# PR9014.net
KiCad netlist of a schematic drawn in EAGLE
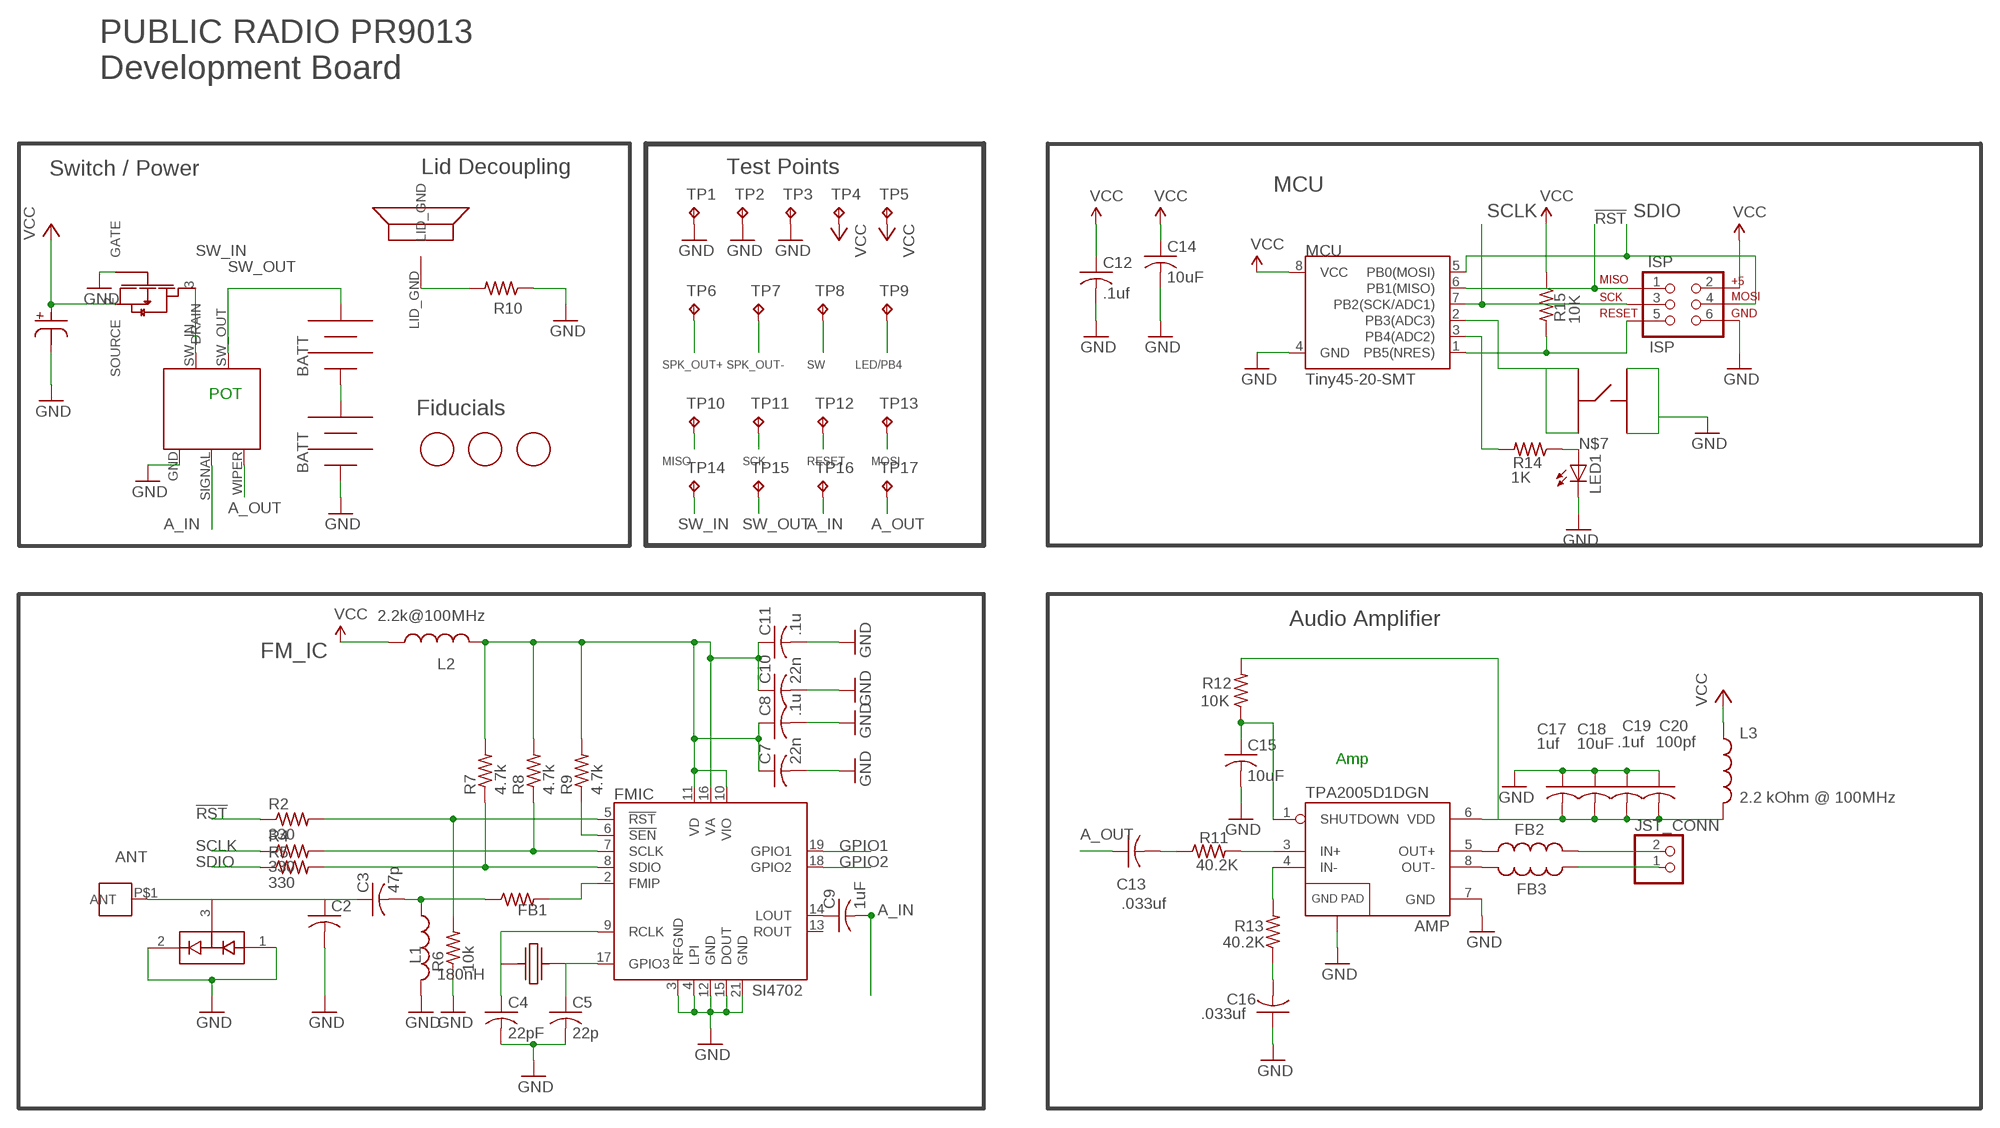
[diagram p0: schematic, sheet 1]

(export (version "E")
  (design (tool "Eeschema 10.0.6"))
  (components
    (comp (ref "AMP")
      (value "TPA2005D1DGN")
      (footprint "eagle-import:POWER-SOP8")
      (libsource (lib "eagle-import") (part "TPA2005D1DGN"))
    )
    (comp (ref "C1")
      (value "220uF")
      (footprint "eagle-import:NICHICON_SERIESUD")
      (libsource (lib "eagle-import") (part "NICHICON_SERIESUD"))
    )
    (comp (ref "C2")
      (value "C-USC0402")
      (footprint "eagle-import:C0402")
      (libsource (lib "eagle-import") (part "C-USC0402"))
    )
    (comp (ref "C3")
      (value "47p")
      (footprint "eagle-import:C0402")
      (libsource (lib "eagle-import") (part "C-USC0402"))
    )
    (comp (ref "C4")
      (value "22pF")
      (footprint "eagle-import:C0402")
      (libsource (lib "eagle-import") (part "C-USC0402"))
    )
    (comp (ref "C5")
      (value "22p")
      (footprint "eagle-import:C0402")
      (libsource (lib "eagle-import") (part "C-USC0402"))
    )
    (comp (ref "C7")
      (value "22n")
      (footprint "eagle-import:C0402")
      (libsource (lib "eagle-import") (part "C-USC0402"))
    )
    (comp (ref "C8")
      (value ".1u")
      (footprint "eagle-import:C0402")
      (libsource (lib "eagle-import") (part "C-USC0402"))
    )
    (comp (ref "C9")
      (value "1uF")
      (footprint "eagle-import:C0402")
      (libsource (lib "eagle-import") (part "C-USC0402"))
    )
    (comp (ref "C10")
      (value "22n")
      (footprint "eagle-import:C0402")
      (libsource (lib "eagle-import") (part "C-USC0402"))
    )
    (comp (ref "C11")
      (value ".1u")
      (footprint "eagle-import:C0402")
      (libsource (lib "eagle-import") (part "C-USC0402"))
    )
    (comp (ref "C12")
      (value ".1uf")
      (footprint "eagle-import:C0402")
      (libsource (lib "eagle-import") (part "C-USC0402"))
    )
    (comp (ref "C13")
      (value ".033uf")
      (footprint "eagle-import:C0402")
      (libsource (lib "eagle-import") (part "C-USC0402"))
    )
    (comp (ref "C14")
      (value "10uF")
      (footprint "eagle-import:C0603")
      (libsource (lib "eagle-import") (part "C-USC0603"))
    )
    (comp (ref "C15")
      (value "10uF")
      (footprint "eagle-import:C0603")
      (libsource (lib "eagle-import") (part "C-USC0603"))
    )
    (comp (ref "C16")
      (value ".033uf")
      (footprint "eagle-import:C0402")
      (libsource (lib "eagle-import") (part "C-USC0402"))
    )
    (comp (ref "C17")
      (value "1uf")
      (footprint "eagle-import:C0402")
      (libsource (lib "eagle-import") (part "C-USC0402"))
    )
    (comp (ref "C18")
      (value "10uF")
      (footprint "eagle-import:C0603")
      (libsource (lib "eagle-import") (part "C-USC0603"))
    )
    (comp (ref "C19")
      (value ".1uf")
      (footprint "eagle-import:C0402")
      (libsource (lib "eagle-import") (part "C-USC0402"))
    )
    (comp (ref "C20")
      (value "100pf")
      (footprint "eagle-import:C0402")
      (libsource (lib "eagle-import") (part "C-USC0402"))
    )
    (comp (ref "D1")
      (value "BAV99")
      (footprint "eagle-import:SOT23")
      (libsource (lib "eagle-import") (part "BAV99"))
    )
    (comp (ref "FB1")
      (value "R-US_R0402")
      (footprint "eagle-import:R0402")
      (libsource (lib "eagle-import") (part "R-US_R0402"))
    )
    (comp (ref "FB2")
      (value "INDUCTOR0805")
      (footprint "eagle-import:0805")
      (libsource (lib "eagle-import") (part "INDUCTOR0805"))
    )
    (comp (ref "FB3")
      (value "INDUCTOR0805")
      (footprint "eagle-import:0805")
      (libsource (lib "eagle-import") (part "INDUCTOR0805"))
    )
    (comp (ref "FET2")
      (value "AO3435")
      (footprint "eagle-import:AO3435")
      (libsource (lib "eagle-import") (part "AO3435"))
    )
    (comp (ref "FMIC")
      (value "SI4702")
      (footprint "eagle-import:SI470X")
      (libsource (lib "eagle-import") (part "SI470X"))
    )
    (comp (ref "ISP")
      (value "ISP")
      (footprint "eagle-import:2X3-NS")
      (libsource (lib "eagle-import") (part "AVR_SPI_PRG_6NS"))
    )
    (comp (ref "J1")
      (value "M3_SCREW_POST")
      (footprint "eagle-import:M3_SCREW_POST")
      (libsource (lib "eagle-import") (part "M3_SCREW_POST"))
    )
    (comp (ref "JP5")
      (value "BK-92_MPD_AA_BATT_CLIP")
      (footprint "eagle-import:BK-92_MPD_AA_BATT_CLIP")
      (libsource (lib "eagle-import") (part "BK-92_MPD_AA_BATT_CLIP"))
    )
    (comp (ref "JP6")
      (value "BK-92_MPD_AA_BATT_CLIP")
      (footprint "eagle-import:BK-92_MPD_AA_BATT_CLIP")
      (libsource (lib "eagle-import") (part "BK-92_MPD_AA_BATT_CLIP"))
    )
    (comp (ref "JST_CONN")
      (value "JST_2PIN-SMT-RA")
      (footprint "eagle-import:JST-PH-2-SMT-RA")
      (libsource (lib "eagle-import") (part "JST_2PIN-SMT-RA"))
    )
    (comp (ref "L1")
      (value "180nH")
      (footprint "eagle-import:0805")
      (libsource (lib "eagle-import") (part "INDUCTOR0805"))
    )
    (comp (ref "L2")
      (value "2.2k@100MHz")
      (footprint "eagle-import:C0402")
      (libsource (lib "eagle-import") (part "INDUCTOR0402"))
    )
    (comp (ref "L3")
      (value "2.2 kOhm @ 100MHz")
      (footprint "eagle-import:C0402")
      (libsource (lib "eagle-import") (part "INDUCTOR0402"))
    )
    (comp (ref "LED1")
      (value "LEDSML0603")
      (footprint "eagle-import:SML0603")
      (libsource (lib "eagle-import") (part "LEDSML0603"))
    )
    (comp (ref "MCU")
      (value "Tiny45-20-SMT")
      (footprint "eagle-import:SO08-EIAJ")
      (libsource (lib "eagle-import") (part "ATTINY45TINY85-20-SMT"))
    )
    (comp (ref "R1")
      (value "RV170SF_TAIWANA_POT_SW")
      (footprint "eagle-import:RV170SF_TAIWANA_POT_SW")
      (libsource (lib "eagle-import") (part "RV170SF_TAIWANA_POT_SW"))
    )
    (comp (ref "R2")
      (value "330")
      (footprint "eagle-import:R0402")
      (libsource (lib "eagle-import") (part "R-US_R0402"))
    )
    (comp (ref "R4")
      (value "330")
      (footprint "eagle-import:R0402")
      (libsource (lib "eagle-import") (part "R-US_R0402"))
    )
    (comp (ref "R5")
      (value "330")
      (footprint "eagle-import:R0402")
      (libsource (lib "eagle-import") (part "R-US_R0402"))
    )
    (comp (ref "R6")
      (value "10k")
      (footprint "eagle-import:R0402")
      (libsource (lib "eagle-import") (part "R-US_R0402"))
    )
    (comp (ref "R7")
      (value "4.7k")
      (footprint "eagle-import:R0402")
      (libsource (lib "eagle-import") (part "R-US_R0402"))
    )
    (comp (ref "R8")
      (value "4.7k")
      (footprint "eagle-import:R0402")
      (libsource (lib "eagle-import") (part "R-US_R0402"))
    )
    (comp (ref "R9")
      (value "4.7k")
      (footprint "eagle-import:R0402")
      (libsource (lib "eagle-import") (part "R-US_R0402"))
    )
    (comp (ref "R10")
      (value "R-US_R0805")
      (footprint "eagle-import:R0805")
      (libsource (lib "eagle-import") (part "R-US_R0805"))
    )
    (comp (ref "R11")
      (value "40.2K")
      (footprint "eagle-import:R0402")
      (libsource (lib "eagle-import") (part "R-US_R0402"))
    )
    (comp (ref "R12")
      (value "10K")
      (footprint "eagle-import:R0402")
      (libsource (lib "eagle-import") (part "R-US_R0402"))
    )
    (comp (ref "R13")
      (value "40.2K")
      (footprint "eagle-import:R0402")
      (libsource (lib "eagle-import") (part "R-US_R0402"))
    )
    (comp (ref "R14")
      (value "1K")
      (footprint "eagle-import:R0402")
      (libsource (lib "eagle-import") (part "R-US_R0402"))
    )
    (comp (ref "R15")
      (value "10K")
      (footprint "eagle-import:R0402")
      (libsource (lib "eagle-import") (part "R-US_R0402"))
    )
    (comp (ref "SW1")
      (value "C&K_PTS645")
      (footprint "eagle-import:C&K_TACTILE_SWITCH")
      (libsource (lib "eagle-import") (part "C&K_PTS645"))
    )
    (comp (ref "TP1")
      (value "TPTP20R")
      (footprint "eagle-import:TP20R")
      (libsource (lib "eagle-import") (part "TPTP20R"))
    )
    (comp (ref "TP2")
      (value "TPTP20R")
      (footprint "eagle-import:TP20R")
      (libsource (lib "eagle-import") (part "TPTP20R"))
    )
    (comp (ref "TP3")
      (value "TPTP20R")
      (footprint "eagle-import:TP20R")
      (libsource (lib "eagle-import") (part "TPTP20R"))
    )
    (comp (ref "TP4")
      (value "TPTP20R")
      (footprint "eagle-import:TP20R")
      (libsource (lib "eagle-import") (part "TPTP20R"))
    )
    (comp (ref "TP5")
      (value "TPTP20R")
      (footprint "eagle-import:TP20R")
      (libsource (lib "eagle-import") (part "TPTP20R"))
    )
    (comp (ref "TP6")
      (value "TPTP20R")
      (footprint "eagle-import:TP20R")
      (libsource (lib "eagle-import") (part "TPTP20R"))
    )
    (comp (ref "TP7")
      (value "TPTP20R")
      (footprint "eagle-import:TP20R")
      (libsource (lib "eagle-import") (part "TPTP20R"))
    )
    (comp (ref "TP8")
      (value "TPTP20R")
      (footprint "eagle-import:TP20R")
      (libsource (lib "eagle-import") (part "TPTP20R"))
    )
    (comp (ref "TP9")
      (value "TPTP20R")
      (footprint "eagle-import:TP20R")
      (libsource (lib "eagle-import") (part "TPTP20R"))
    )
    (comp (ref "TP10")
      (value "TPTP20R")
      (footprint "eagle-import:TP20R")
      (libsource (lib "eagle-import") (part "TPTP20R"))
    )
    (comp (ref "TP11")
      (value "TPTP20R")
      (footprint "eagle-import:TP20R")
      (libsource (lib "eagle-import") (part "TPTP20R"))
    )
    (comp (ref "TP12")
      (value "TPTP20R")
      (footprint "eagle-import:TP20R")
      (libsource (lib "eagle-import") (part "TPTP20R"))
    )
    (comp (ref "TP13")
      (value "TPTP20R")
      (footprint "eagle-import:TP20R")
      (libsource (lib "eagle-import") (part "TPTP20R"))
    )
    (comp (ref "TP14")
      (value "TPTP20R")
      (footprint "eagle-import:TP20R")
      (libsource (lib "eagle-import") (part "TPTP20R"))
    )
    (comp (ref "TP15")
      (value "TPTP20R")
      (footprint "eagle-import:TP20R")
      (libsource (lib "eagle-import") (part "TPTP20R"))
    )
    (comp (ref "TP16")
      (value "TPTP20R")
      (footprint "eagle-import:TP20R")
      (libsource (lib "eagle-import") (part "TPTP20R"))
    )
    (comp (ref "TP17")
      (value "TPTP20R")
      (footprint "eagle-import:TP20R")
      (libsource (lib "eagle-import") (part "TPTP20R"))
    )
    (comp (ref "U$1")
      (value "CE32A_FOR_JST")
      (footprint "eagle-import:CE32A_FOR_JST")
      (libsource (lib "eagle-import") (part "PR_Parts_Library_CE32A_FOR_JST"))
    )
    (comp (ref "U$3")
      (value "FIDUCIAL")
      (footprint "eagle-import:FIDUCIAL_1MM")
      (libsource (lib "eagle-import") (part "FIDUCIAL"))
    )
    (comp (ref "U$4")
      (value "FIDUCIAL")
      (footprint "eagle-import:FIDUCIAL_1MM")
      (libsource (lib "eagle-import") (part "FIDUCIAL"))
    )
    (comp (ref "U$5")
      (value "FIDUCIAL")
      (footprint "eagle-import:FIDUCIAL_1MM")
      (libsource (lib "eagle-import") (part "FIDUCIAL"))
    )
    (comp (ref "U$6")
      (value "ABS25XTAL")
      (footprint "eagle-import:ABS25XTAL")
      (libsource (lib "eagle-import") (part "ABS25XTAL"))
    )
  )
  (nets
    (net (code "1") (name "/ANT") (class "Default")
      (node (ref "C2") (pin "1") (pinfunction "1_1") (pintype "passive"))
      (node (ref "C3") (pin "1") (pinfunction "1_1") (pintype "passive"))
      (node (ref "D1") (pin "3") (pinfunction "COM_3") (pintype "bidirectional"))
      (node (ref "J1") (pin "P$1") (pinfunction "ANT_P$1") (pintype "bidirectional"))
    )
    (net (code "2") (name "/A_IN") (class "Default")
      (node (ref "C9") (pin "2") (pinfunction "2_2") (pintype "passive"))
      (node (ref "R1") (pin "SIGNAL") (pinfunction "SIGNAL_SIGNAL") (pintype "bidirectional"))
      (node (ref "TP16") (pin "TP") (pinfunction "TP_TP") (pintype "input"))
    )
    (net (code "3") (name "/A_OUT") (class "Default")
      (node (ref "C13") (pin "1") (pinfunction "1_1") (pintype "passive"))
      (node (ref "R1") (pin "WIPER") (pinfunction "WIPER_WIPER") (pintype "bidirectional"))
      (node (ref "TP17") (pin "TP") (pinfunction "TP_TP") (pintype "input"))
    )
    (net (code "4") (name "/GPIO1") (class "Default")
      (node (ref "FMIC") (pin "19") (pinfunction "GPIO1_19") (pintype "bidirectional"))
    )
    (net (code "5") (name "/GPIO2") (class "Default")
      (node (ref "FMIC") (pin "18") (pinfunction "GPIO2_18") (pintype "bidirectional"))
    )
    (net (code "6") (name "/LED{slash}PB4") (class "Default")
      (node (ref "MCU") (pin "3") (pinfunction "PB4(ADC2)_3") (pintype "bidirectional"))
      (node (ref "R14") (pin "2") (pinfunction "2_2") (pintype "passive"))
      (node (ref "TP9") (pin "TP") (pinfunction "TP_TP") (pintype "input"))
    )
    (net (code "7") (name "/N$7") (class "Default")
      (node (ref "LED1") (pin "A") (pinfunction "A_A") (pintype "passive"))
      (node (ref "R14") (pin "1") (pinfunction "1_1") (pintype "passive"))
    )
    (net (code "8") (name "/RESET") (class "Default")
      (node (ref "ISP") (pin "5") (pinfunction "5_5") (pintype "passive"))
      (node (ref "MCU") (pin "1") (pinfunction "PB5(NRES)_1") (pintype "bidirectional"))
      (node (ref "R15") (pin "2") (pinfunction "2_2") (pintype "passive"))
      (node (ref "TP12") (pin "TP") (pinfunction "TP_TP") (pintype "input"))
    )
    (net (code "9") (name "/SCLK") (class "Default")
      (node (ref "ISP") (pin "3") (pinfunction "3_3") (pintype "passive"))
      (node (ref "MCU") (pin "7") (pinfunction "PB2(SCK/ADC1)_7") (pintype "bidirectional"))
      (node (ref "R4") (pin "1") (pinfunction "1_1") (pintype "passive"))
      (node (ref "TP11") (pin "TP") (pinfunction "TP_TP") (pintype "input"))
    )
    (net (code "10") (name "/SDIO") (class "Default")
      (node (ref "ISP") (pin "4") (pinfunction "4_4") (pintype "passive"))
      (node (ref "MCU") (pin "5") (pinfunction "PB0(MOSI)_5") (pintype "bidirectional"))
      (node (ref "R5") (pin "1") (pinfunction "1_1") (pintype "passive"))
      (node (ref "TP13") (pin "TP") (pinfunction "TP_TP") (pintype "input"))
    )
    (net (code "11") (name "/SPK_OUT+") (class "Default")
      (node (ref "FB2") (pin "2") (pinfunction "2_2") (pintype "passive"))
      (node (ref "JST_CONN") (pin "2") (pinfunction "1_2") (pintype "passive"))
      (node (ref "TP6") (pin "TP") (pinfunction "TP_TP") (pintype "input"))
    )
    (net (code "12") (name "/SPK_OUT-") (class "Default")
      (node (ref "FB3") (pin "1") (pinfunction "1_1") (pintype "passive"))
      (node (ref "JST_CONN") (pin "1") (pinfunction "2_1") (pintype "passive"))
      (node (ref "TP7") (pin "TP") (pinfunction "TP_TP") (pintype "input"))
    )
    (net (code "13") (name "/SW") (class "Default")
      (node (ref "MCU") (pin "2") (pinfunction "PB3(ADC3)_2") (pintype "bidirectional"))
      (node (ref "SW1") (pin "P$3") (pinfunction "P$3_P$3") (pintype "bidirectional"))
      (node (ref "SW1") (pin "P$4") (pinfunction "P$4_P$4") (pintype "bidirectional"))
      (node (ref "TP8") (pin "TP") (pinfunction "TP_TP") (pintype "input"))
    )
    (net (code "14") (name "/SW_IN") (class "Default")
      (node (ref "FET2") (pin "3") (pinfunction "DRAIN_3") (pintype "bidirectional"))
      (node (ref "R1") (pin "SW_IN") (pinfunction "SW_IN_SW_IN") (pintype "bidirectional"))
      (node (ref "TP14") (pin "TP") (pinfunction "TP_TP") (pintype "input"))
    )
    (net (code "15") (name "/SW_OUT") (class "Default")
      (node (ref "JP5") (pin "POS") (pinfunction "POS_POS") (pintype "bidirectional"))
      (node (ref "JP5") (pin "POS@2") (pinfunction "POS_POS@2") (pintype "bidirectional"))
      (node (ref "R1") (pin "SW_OUT") (pinfunction "SW_OUT_SW_OUT") (pintype "bidirectional"))
      (node (ref "TP15") (pin "TP") (pinfunction "TP_TP") (pintype "input"))
    )
    (net (code "16") (name "/~{RST}") (class "Default")
      (node (ref "ISP") (pin "1") (pinfunction "1_1") (pintype "passive"))
      (node (ref "MCU") (pin "6") (pinfunction "PB1(MISO)_6") (pintype "bidirectional"))
      (node (ref "R2") (pin "1") (pinfunction "1_1") (pintype "passive"))
      (node (ref "TP10") (pin "TP") (pinfunction "TP_TP") (pintype "input"))
    )
    (net (code "17") (name "GND") (class "Default")
      (node (ref "AMP") (pin "7") (pinfunction "GND_7") (pintype "power_in"))
      (node (ref "AMP") (pin "9") (pinfunction "GND_9") (pintype "power_in"))
      (node (ref "C1") (pin "P$2") (pinfunction "P$2_P$2") (pintype "bidirectional"))
      (node (ref "C10") (pin "2") (pinfunction "2_2") (pintype "passive"))
      (node (ref "C11") (pin "2") (pinfunction "2_2") (pintype "passive"))
      (node (ref "C12") (pin "2") (pinfunction "2_2") (pintype "passive"))
      (node (ref "C14") (pin "2") (pinfunction "2_2") (pintype "passive"))
      (node (ref "C15") (pin "2") (pinfunction "2_2") (pintype "passive"))
      (node (ref "C16") (pin "1") (pinfunction "1_1") (pintype "passive"))
      (node (ref "C17") (pin "1") (pinfunction "1_1") (pintype "passive"))
      (node (ref "C18") (pin "1") (pinfunction "1_1") (pintype "passive"))
      (node (ref "C19") (pin "1") (pinfunction "1_1") (pintype "passive"))
      (node (ref "C2") (pin "2") (pinfunction "2_2") (pintype "passive"))
      (node (ref "C20") (pin "1") (pinfunction "1_1") (pintype "passive"))
      (node (ref "C4") (pin "2") (pinfunction "2_2") (pintype "passive"))
      (node (ref "C5") (pin "2") (pinfunction "2_2") (pintype "passive"))
      (node (ref "C7") (pin "2") (pinfunction "2_2") (pintype "passive"))
      (node (ref "C8") (pin "2") (pinfunction "2_2") (pintype "passive"))
      (node (ref "D1") (pin "1") (pinfunction "A1_1") (pintype "bidirectional"))
      (node (ref "D1") (pin "2") (pinfunction "C2_2") (pintype "bidirectional"))
      (node (ref "FET2") (pin "1") (pinfunction "GATE_1") (pintype "bidirectional"))
      (node (ref "FMIC") (pin "12") (pinfunction "GND_12") (pintype "bidirectional"))
      (node (ref "FMIC") (pin "15") (pinfunction "DOUT_15") (pintype "bidirectional"))
      (node (ref "FMIC") (pin "21") (pinfunction "GND_21") (pintype "bidirectional"))
      (node (ref "FMIC") (pin "3") (pinfunction "RFGND_3") (pintype "bidirectional"))
      (node (ref "FMIC") (pin "4") (pinfunction "LPI_4") (pintype "bidirectional"))
      (node (ref "ISP") (pin "6") (pinfunction "6_6") (pintype "passive"))
      (node (ref "JP6") (pin "NEG") (pinfunction "NEG_NEG") (pintype "bidirectional"))
      (node (ref "JP6") (pin "NEG@2") (pinfunction "NEG_NEG@2") (pintype "bidirectional"))
      (node (ref "L1") (pin "2") (pinfunction "2_2") (pintype "passive"))
      (node (ref "LED1") (pin "C") (pinfunction "C_C") (pintype "passive"))
      (node (ref "MCU") (pin "4") (pinfunction "GND_4") (pintype "bidirectional"))
      (node (ref "R1") (pin "GND") (pinfunction "GND_GND") (pintype "bidirectional"))
      (node (ref "R10") (pin "1") (pinfunction "1_1") (pintype "passive"))
      (node (ref "R6") (pin "1") (pinfunction "1_1") (pintype "passive"))
      (node (ref "SW1") (pin "P$1") (pinfunction "P$1_P$1") (pintype "bidirectional"))
      (node (ref "SW1") (pin "P$2") (pinfunction "P$2_P$2") (pintype "bidirectional"))
      (node (ref "TP1") (pin "TP") (pinfunction "TP_TP") (pintype "input"))
      (node (ref "TP2") (pin "TP") (pinfunction "TP_TP") (pintype "input"))
      (node (ref "TP3") (pin "TP") (pinfunction "TP_TP") (pintype "input"))
    )
    (net (code "18") (name "Net-(AMP-IN+)") (class "Default")
      (node (ref "AMP") (pin "3") (pinfunction "IN+_3") (pintype "bidirectional"))
      (node (ref "R11") (pin "2") (pinfunction "2_2") (pintype "passive"))
    )
    (net (code "19") (name "Net-(AMP-IN-)") (class "Default")
      (node (ref "AMP") (pin "4") (pinfunction "IN-_4") (pintype "bidirectional"))
      (node (ref "R13") (pin "2") (pinfunction "2_2") (pintype "passive"))
    )
    (net (code "20") (name "Net-(AMP-OUT+)") (class "Default")
      (node (ref "AMP") (pin "5") (pinfunction "OUT+_5") (pintype "bidirectional"))
      (node (ref "FB2") (pin "1") (pinfunction "1_1") (pintype "passive"))
    )
    (net (code "21") (name "Net-(AMP-OUT-)") (class "Default")
      (node (ref "AMP") (pin "8") (pinfunction "OUT-_8") (pintype "bidirectional"))
      (node (ref "FB3") (pin "2") (pinfunction "2_2") (pintype "passive"))
    )
    (net (code "22") (name "Net-(AMP-SHUTDOWN)") (class "Default")
      (node (ref "AMP") (pin "1") (pinfunction "SHUTDOWN_1") (pintype "input"))
      (node (ref "C15") (pin "1") (pinfunction "1_1") (pintype "passive"))
      (node (ref "R12") (pin "1") (pinfunction "1_1") (pintype "passive"))
    )
    (net (code "23") (name "Net-(AMP-VDD)") (class "Default")
      (node (ref "AMP") (pin "6") (pinfunction "VDD_6") (pintype "power_in"))
      (node (ref "C17") (pin "2") (pinfunction "2_2") (pintype "passive"))
      (node (ref "C18") (pin "2") (pinfunction "2_2") (pintype "passive"))
      (node (ref "C19") (pin "2") (pinfunction "2_2") (pintype "passive"))
      (node (ref "C20") (pin "2") (pinfunction "2_2") (pintype "passive"))
      (node (ref "L3") (pin "2") (pinfunction "2_2") (pintype "passive"))
      (node (ref "R12") (pin "2") (pinfunction "2_2") (pintype "passive"))
    )
    (net (code "24") (name "Net-(C3-Pad2)") (class "Default")
      (node (ref "C3") (pin "2") (pinfunction "2_2") (pintype "passive"))
      (node (ref "FB1") (pin "1") (pinfunction "1_1") (pintype "passive"))
      (node (ref "L1") (pin "1") (pinfunction "1_1") (pintype "passive"))
    )
    (net (code "25") (name "Net-(C13-Pad2)") (class "Default")
      (node (ref "C13") (pin "2") (pinfunction "2_2") (pintype "passive"))
      (node (ref "R11") (pin "1") (pinfunction "1_1") (pintype "passive"))
    )
    (net (code "26") (name "Net-(C16-Pad2)") (class "Default")
      (node (ref "C16") (pin "2") (pinfunction "2_2") (pintype "passive"))
      (node (ref "R13") (pin "1") (pinfunction "1_1") (pintype "passive"))
    )
    (net (code "27") (name "Net-(FMIC-FMIP)") (class "Default")
      (node (ref "FB1") (pin "2") (pinfunction "2_2") (pintype "passive"))
      (node (ref "FMIC") (pin "2") (pinfunction "FMIP_2") (pintype "bidirectional"))
    )
    (net (code "28") (name "Net-(FMIC-GPIO3)") (class "Default")
      (node (ref "C5") (pin "1") (pinfunction "1_1") (pintype "passive"))
      (node (ref "FMIC") (pin "17") (pinfunction "GPIO3_17") (pintype "bidirectional"))
      (node (ref "U$6") (pin "P$4") (pinfunction "P$4_P$4") (pintype "bidirectional"))
    )
    (net (code "29") (name "Net-(FMIC-LOUT)") (class "Default")
      (node (ref "C9") (pin "1") (pinfunction "1_1") (pintype "passive"))
      (node (ref "FMIC") (pin "14") (pinfunction "LOUT_14") (pintype "bidirectional"))
    )
    (net (code "30") (name "Net-(FMIC-RCLK)") (class "Default")
      (node (ref "C4") (pin "1") (pinfunction "1_1") (pintype "passive"))
      (node (ref "FMIC") (pin "9") (pinfunction "RCLK_9") (pintype "bidirectional"))
      (node (ref "U$6") (pin "P$1") (pinfunction "P$1_P$1") (pintype "bidirectional"))
    )
    (net (code "31") (name "Net-(FMIC-SCLK)") (class "Default")
      (node (ref "FMIC") (pin "7") (pinfunction "SCLK_7") (pintype "bidirectional"))
      (node (ref "R4") (pin "2") (pinfunction "2_2") (pintype "passive"))
      (node (ref "R8") (pin "1") (pinfunction "1_1") (pintype "passive"))
    )
    (net (code "32") (name "Net-(FMIC-SDIO)") (class "Default")
      (node (ref "FMIC") (pin "8") (pinfunction "SDIO_8") (pintype "bidirectional"))
      (node (ref "R5") (pin "2") (pinfunction "2_2") (pintype "passive"))
      (node (ref "R7") (pin "1") (pinfunction "1_1") (pintype "passive"))
    )
    (net (code "33") (name "Net-(FMIC-VA)") (class "Default")
      (node (ref "C10") (pin "1") (pinfunction "1_1") (pintype "passive"))
      (node (ref "C11") (pin "1") (pinfunction "1_1") (pintype "passive"))
      (node (ref "C7") (pin "1") (pinfunction "1_1") (pintype "passive"))
      (node (ref "C8") (pin "1") (pinfunction "1_1") (pintype "passive"))
      (node (ref "FMIC") (pin "10") (pinfunction "VIO_10") (pintype "bidirectional"))
      (node (ref "FMIC") (pin "11") (pinfunction "VD_11") (pintype "bidirectional"))
      (node (ref "FMIC") (pin "16") (pinfunction "VA_16") (pintype "bidirectional"))
      (node (ref "L2") (pin "2") (pinfunction "2_2") (pintype "passive"))
      (node (ref "R7") (pin "2") (pinfunction "2_2") (pintype "passive"))
      (node (ref "R8") (pin "2") (pinfunction "2_2") (pintype "passive"))
      (node (ref "R9") (pin "2") (pinfunction "2_2") (pintype "passive"))
    )
    (net (code "34") (name "Net-(FMIC-~{RST})") (class "Default")
      (node (ref "FMIC") (pin "5") (pinfunction "~{RST}_5") (pintype "bidirectional"))
      (node (ref "R2") (pin "2") (pinfunction "2_2") (pintype "passive"))
      (node (ref "R6") (pin "2") (pinfunction "2_2") (pintype "passive"))
    )
    (net (code "35") (name "Net-(FMIC-~{SEN})") (class "Default")
      (node (ref "FMIC") (pin "6") (pinfunction "~{SEN}_6") (pintype "bidirectional"))
      (node (ref "R9") (pin "1") (pinfunction "1_1") (pintype "passive"))
    )
    (net (code "36") (name "Net-(JP5-NEG-PadNEG@2)") (class "Default")
      (node (ref "JP5") (pin "NEG") (pinfunction "NEG_NEG") (pintype "bidirectional"))
      (node (ref "JP5") (pin "NEG@2") (pinfunction "NEG_NEG@2") (pintype "bidirectional"))
      (node (ref "JP6") (pin "POS") (pinfunction "POS_POS") (pintype "bidirectional"))
      (node (ref "JP6") (pin "POS@2") (pinfunction "POS_POS@2") (pintype "bidirectional"))
    )
    (net (code "37") (name "Net-(R10-Pad2)") (class "Default")
      (node (ref "R10") (pin "2") (pinfunction "2_2") (pintype "passive"))
      (node (ref "U$1") (pin "LID_GND") (pinfunction "LID_GND_LID_GND") (pintype "bidirectional"))
    )
    (net (code "38") (name "VCC") (class "Default")
      (node (ref "C1") (pin "P$1") (pinfunction "P$1_P$1") (pintype "bidirectional"))
      (node (ref "C12") (pin "1") (pinfunction "1_1") (pintype "passive"))
      (node (ref "C14") (pin "1") (pinfunction "1_1") (pintype "passive"))
      (node (ref "FET2") (pin "2") (pinfunction "SOURCE_2") (pintype "bidirectional"))
      (node (ref "ISP") (pin "2") (pinfunction "2_2") (pintype "passive"))
      (node (ref "L2") (pin "1") (pinfunction "1_1") (pintype "passive"))
      (node (ref "L3") (pin "1") (pinfunction "1_1") (pintype "passive"))
      (node (ref "MCU") (pin "8") (pinfunction "VCC_8") (pintype "bidirectional"))
      (node (ref "R15") (pin "1") (pinfunction "1_1") (pintype "passive"))
      (node (ref "TP4") (pin "TP") (pinfunction "TP_TP") (pintype "input"))
      (node (ref "TP5") (pin "TP") (pinfunction "TP_TP") (pintype "input"))
    )
    (net (code "39") (name "unconnected-(FMIC-ROUT-Pad13)") (class "Default")
      (node (ref "FMIC") (pin "13") (pinfunction "ROUT_13") (pintype "bidirectional"))
    )
  )
)
